# Power.net
KiCad netlist of a schematic drawn in Altium Designer
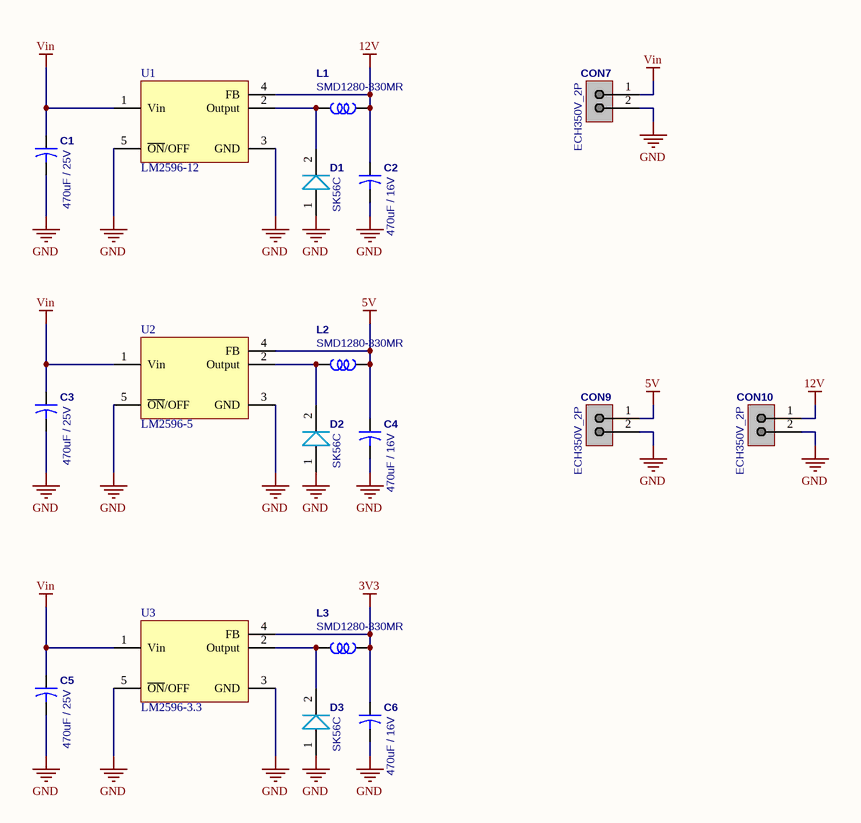
[diagram p0: Power.SchDoc]

(export (version "E")
  (design (tool "Eeschema 10.0.6"))
  (components
    (comp (ref "C1")
      (value "470uF / 25V")
      (footprint "Cap470u_25V")
      (description "Capacitor, 470uF / 25V / 10PI / SMD, 10mm")
      (fields (field (name "PUBLISHER") "Altium Limited"))
      (libsource (lib "SensoMonitor") (part "Cap470u_25V"))
    )
    (comp (ref "C2")
      (value "470uF / 16V")
      (footprint "Cap470u_16V")
      (description "Capacitor, 470uF / 25V / 8PI / SMD, 8mm")
      (fields (field (name "PUBLISHER") "Altium Limited"))
      (libsource (lib "SensoMonitor") (part "Cap470u_16V"))
    )
    (comp (ref "C3")
      (value "470uF / 25V")
      (footprint "Cap470u_25V")
      (description "Capacitor, 470uF / 25V / 10PI / SMD, 10mm")
      (fields (field (name "PUBLISHER") "Altium Limited"))
      (libsource (lib "SensoMonitor") (part "Cap470u_25V"))
    )
    (comp (ref "C4")
      (value "470uF / 16V")
      (footprint "Cap470u_16V")
      (description "Capacitor, 470uF / 25V / 8PI / SMD, 8mm")
      (fields (field (name "PUBLISHER") "Altium Limited"))
      (libsource (lib "SensoMonitor") (part "Cap470u_16V"))
    )
    (comp (ref "C5")
      (value "470uF / 25V")
      (footprint "Cap470u_25V")
      (description "Capacitor, 470uF / 25V / 10PI / SMD, 10mm")
      (fields (field (name "PUBLISHER") "Altium Limited"))
      (libsource (lib "SensoMonitor") (part "Cap470u_25V"))
    )
    (comp (ref "C6")
      (value "470uF / 16V")
      (footprint "Cap470u_16V")
      (description "Capacitor, 470uF / 25V / 8PI / SMD, 8mm")
      (fields (field (name "PUBLISHER") "Altium Limited"))
      (libsource (lib "SensoMonitor") (part "Cap470u_16V"))
    )
    (comp (ref "CON7")
      (value "ECH350V_2P")
      (footprint "CON2P_ECH350V")
      (description "Connector, Terminal block 2p_ECH350V")
      (libsource (lib "SensoMonitor") (part "CON2P_ECH350V"))
    )
    (comp (ref "CON9")
      (value "ECH350V_2P")
      (footprint "CON2P_ECH350V")
      (description "Connector, Terminal block 2p_ECH350V")
      (libsource (lib "SensoMonitor") (part "CON2P_ECH350V"))
    )
    (comp (ref "CON10")
      (value "ECH350V_2P")
      (footprint "CON2P_ECH350V")
      (description "Connector, Terminal block 2p_ECH350V")
      (libsource (lib "SensoMonitor") (part "CON2P_ECH350V"))
    )
    (comp (ref "D1")
      (value "SK56C")
      (footprint "DIODE_SK56C")
      (description "Schottky Barrier Rectifier SK56C")
      (libsource (lib "SensoMonitor") (part "DIODE_SK56C"))
    )
    (comp (ref "D2")
      (value "SK56C")
      (footprint "DIODE_SK56C")
      (description "Schottky Barrier Rectifier SK56C")
      (libsource (lib "SensoMonitor") (part "DIODE_SK56C"))
    )
    (comp (ref "D3")
      (value "SK56C")
      (footprint "DIODE_SK56C")
      (description "Schottky Barrier Rectifier SK56C")
      (libsource (lib "SensoMonitor") (part "DIODE_SK56C"))
    )
    (comp (ref "L1")
      (value "SMD1280-330MR")
      (footprint "IND33uCoil")
      (description "12.5mmX12.5mmX8.0mm smd Inductor, Hanam electornic.")
      (libsource (lib "SensoMonitor") (part "IND33uCoil"))
    )
    (comp (ref "L2")
      (value "SMD1280-330MR")
      (footprint "IND33uCoil")
      (description "12.5mmX12.5mmX8.0mm smd Inductor, Hanam electornic.")
      (libsource (lib "SensoMonitor") (part "IND33uCoil"))
    )
    (comp (ref "L3")
      (value "SMD1280-330MR")
      (footprint "IND33uCoil")
      (description "12.5mmX12.5mmX8.0mm smd Inductor, Hanam electornic.")
      (libsource (lib "SensoMonitor") (part "IND33uCoil"))
    )
    (comp (ref "U1")
      (value "LM2596-12")
      (footprint "LM2596SX")
      (description "LM2596 SIMPLE SWITCHER® Power Converter 150-kHz  3-A Step-Down Voltage Regulator")
      (libsource (lib "SensoMonitor") (part "LM2596-12"))
    )
    (comp (ref "U2")
      (value "LM2596-5")
      (footprint "LM2596SX")
      (description "LM2596 SIMPLE SWITCHER® Power Converter 150-kHz  3-A Step-Down Voltage Regulator")
      (libsource (lib "SensoMonitor") (part "LM2596-5"))
    )
    (comp (ref "U3")
      (value "LM2596-3.3")
      (footprint "LM2596SX")
      (description "LM2596 SIMPLE SWITCHER® Power Converter 150-kHz  3-A Step-Down Voltage Regulator")
      (libsource (lib "SensoMonitor") (part "LM2596-3.3"))
    )
  )
  (nets
    (net (code "1") (name "3V3") (class "Default")
      (node (ref "C6") (pin "1") (pinfunction "1_1") (pintype "passive"))
      (node (ref "L3") (pin "1") (pintype "passive"))
      (node (ref "U3") (pin "4") (pinfunction "FB_4") (pintype "passive"))
    )
    (net (code "2") (name "5V") (class "Default")
      (node (ref "C4") (pin "1") (pinfunction "1_1") (pintype "passive"))
      (node (ref "CON9") (pin "1") (pinfunction "150_1") (pintype "passive"))
      (node (ref "L2") (pin "1") (pintype "passive"))
      (node (ref "U2") (pin "4") (pinfunction "FB_4") (pintype "passive"))
    )
    (net (code "3") (name "12V") (class "Default")
      (node (ref "C2") (pin "1") (pinfunction "1_1") (pintype "passive"))
      (node (ref "CON10") (pin "1") (pinfunction "150_1") (pintype "passive"))
      (node (ref "L1") (pin "1") (pintype "passive"))
      (node (ref "U1") (pin "4") (pinfunction "FB_4") (pintype "passive"))
    )
    (net (code "4") (name "GND") (class "Default")
      (node (ref "C1") (pin "2") (pinfunction "2_2") (pintype "passive"))
      (node (ref "C2") (pin "2") (pinfunction "2_2") (pintype "passive"))
      (node (ref "C3") (pin "2") (pinfunction "2_2") (pintype "passive"))
      (node (ref "C4") (pin "2") (pinfunction "2_2") (pintype "passive"))
      (node (ref "C5") (pin "2") (pinfunction "2_2") (pintype "passive"))
      (node (ref "C6") (pin "2") (pinfunction "2_2") (pintype "passive"))
      (node (ref "CON10") (pin "2") (pinfunction "150_2") (pintype "passive"))
      (node (ref "CON7") (pin "2") (pinfunction "150_2") (pintype "passive"))
      (node (ref "CON9") (pin "2") (pinfunction "150_2") (pintype "passive"))
      (node (ref "D1") (pin "1") (pintype "passive"))
      (node (ref "D2") (pin "1") (pintype "passive"))
      (node (ref "D3") (pin "1") (pintype "passive"))
      (node (ref "U1") (pin "3") (pinfunction "GND_3") (pintype "passive"))
      (node (ref "U1") (pin "5") (pinfunction "~{ON}/OFF_5") (pintype "passive"))
      (node (ref "U2") (pin "3") (pinfunction "GND_3") (pintype "passive"))
      (node (ref "U2") (pin "5") (pinfunction "~{ON}/OFF_5") (pintype "passive"))
      (node (ref "U3") (pin "3") (pinfunction "GND_3") (pintype "passive"))
      (node (ref "U3") (pin "5") (pinfunction "~{ON}/OFF_5") (pintype "passive"))
    )
    (net (code "5") (name "Net-(U1-Output)") (class "Default")
      (node (ref "D1") (pin "2") (pintype "passive"))
      (node (ref "L1") (pin "2") (pintype "passive"))
      (node (ref "U1") (pin "2") (pinfunction "Output_2") (pintype "passive"))
    )
    (net (code "6") (name "Net-(U2-Output)") (class "Default")
      (node (ref "D2") (pin "2") (pintype "passive"))
      (node (ref "L2") (pin "2") (pintype "passive"))
      (node (ref "U2") (pin "2") (pinfunction "Output_2") (pintype "passive"))
    )
    (net (code "7") (name "Net-(U3-Output)") (class "Default")
      (node (ref "D3") (pin "2") (pintype "passive"))
      (node (ref "L3") (pin "2") (pintype "passive"))
      (node (ref "U3") (pin "2") (pinfunction "Output_2") (pintype "passive"))
    )
    (net (code "8") (name "Vin") (class "Default")
      (node (ref "C1") (pin "1") (pinfunction "1_1") (pintype "passive"))
      (node (ref "C3") (pin "1") (pinfunction "1_1") (pintype "passive"))
      (node (ref "C5") (pin "1") (pinfunction "1_1") (pintype "passive"))
      (node (ref "CON7") (pin "1") (pinfunction "150_1") (pintype "passive"))
      (node (ref "U1") (pin "1") (pinfunction "Vin_1") (pintype "passive"))
      (node (ref "U2") (pin "1") (pinfunction "Vin_1") (pintype "passive"))
      (node (ref "U3") (pin "1") (pinfunction "Vin_1") (pintype "passive"))
    )
  )
)
